# 24S_Sensor_Schematic_v9.net
KiCad netlist of a schematic drawn in EAGLE
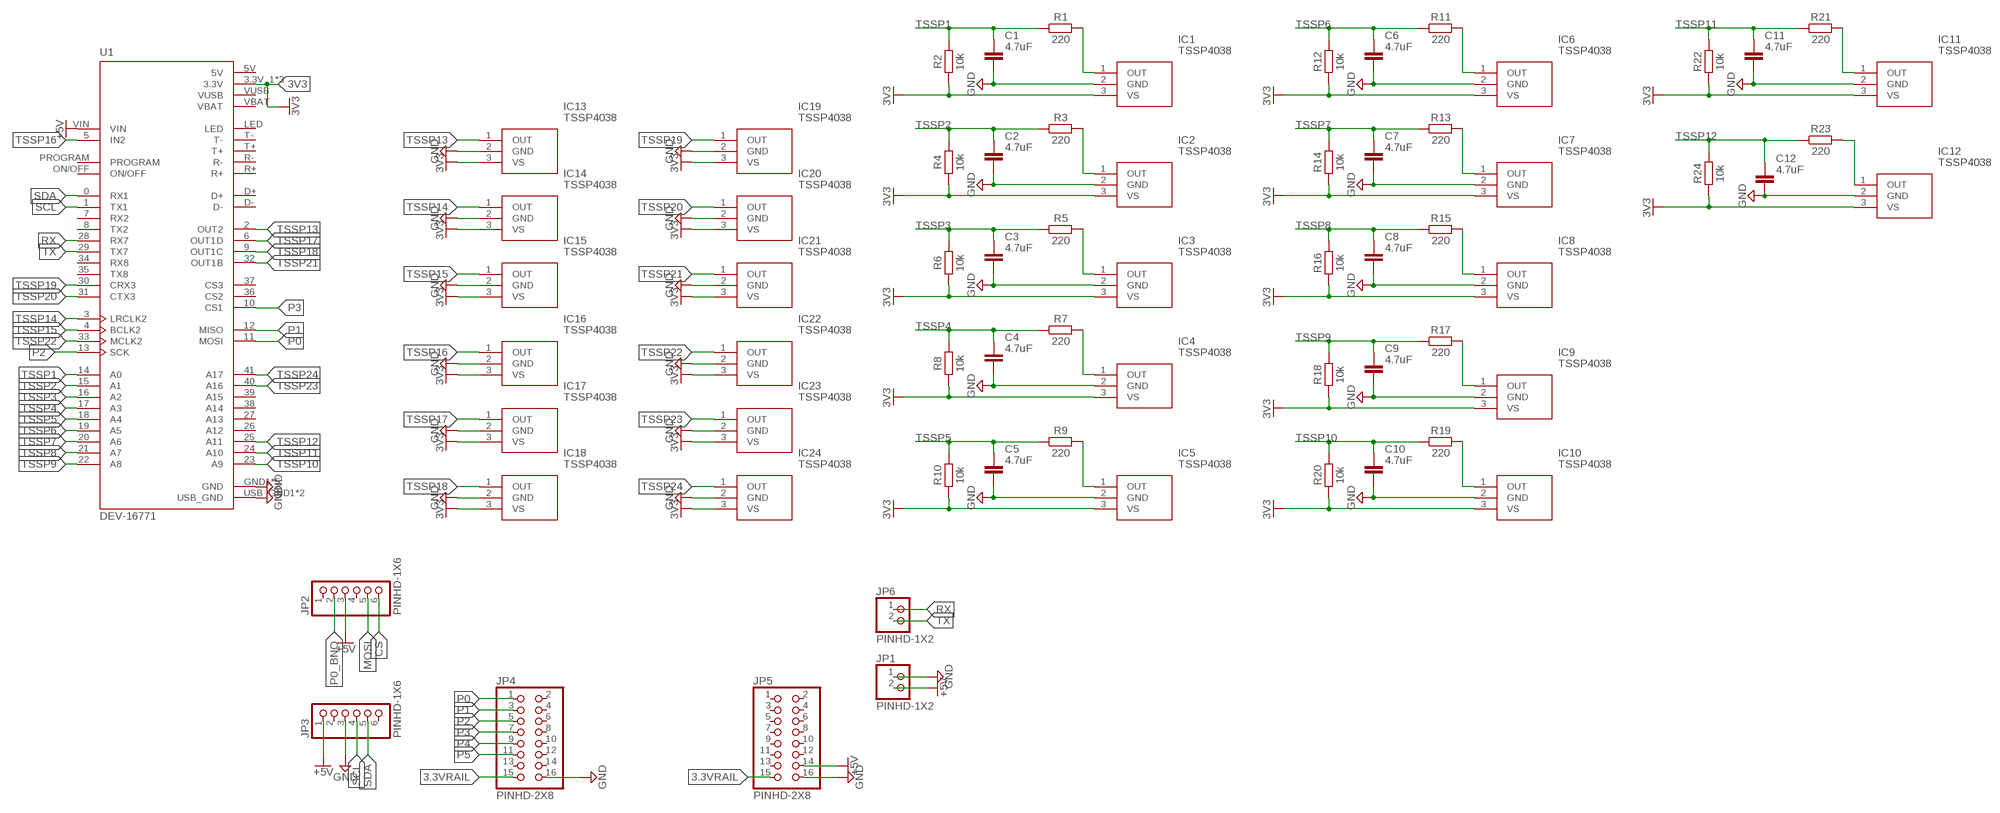
[diagram p0: schematic, sheet 1]

(export (version "E")
  (design (tool "Eeschema 10.0.6"))
  (components
    (comp (ref "C1")
      (value "4.7uF")
      (footprint "eagle-import:CAPC3216X135")
      (libsource (lib "eagle-import") (part "CCHIP-1206(3216-METRIC)_"))
    )
    (comp (ref "C2")
      (value "4.7uF")
      (footprint "eagle-import:CAPC3216X135")
      (libsource (lib "eagle-import") (part "CCHIP-1206(3216-METRIC)_"))
    )
    (comp (ref "C3")
      (value "4.7uF")
      (footprint "eagle-import:CAPC3216X135")
      (libsource (lib "eagle-import") (part "CCHIP-1206(3216-METRIC)_"))
    )
    (comp (ref "C4")
      (value "4.7uF")
      (footprint "eagle-import:CAPC3216X135")
      (libsource (lib "eagle-import") (part "CCHIP-1206(3216-METRIC)_"))
    )
    (comp (ref "C5")
      (value "4.7uF")
      (footprint "eagle-import:CAPC3216X135")
      (libsource (lib "eagle-import") (part "CCHIP-1206(3216-METRIC)_"))
    )
    (comp (ref "C6")
      (value "4.7uF")
      (footprint "eagle-import:CAPC3216X135")
      (libsource (lib "eagle-import") (part "CCHIP-1206(3216-METRIC)_"))
    )
    (comp (ref "C7")
      (value "4.7uF")
      (footprint "eagle-import:CAPC3216X135")
      (libsource (lib "eagle-import") (part "CCHIP-1206(3216-METRIC)_"))
    )
    (comp (ref "C8")
      (value "4.7uF")
      (footprint "eagle-import:CAPC3216X135")
      (libsource (lib "eagle-import") (part "CCHIP-1206(3216-METRIC)_"))
    )
    (comp (ref "C9")
      (value "4.7uF")
      (footprint "eagle-import:CAPC3216X135")
      (libsource (lib "eagle-import") (part "CCHIP-1206(3216-METRIC)_"))
    )
    (comp (ref "C10")
      (value "4.7uF")
      (footprint "eagle-import:CAPC3216X135")
      (libsource (lib "eagle-import") (part "CCHIP-1206(3216-METRIC)_"))
    )
    (comp (ref "C11")
      (value "4.7uF")
      (footprint "eagle-import:CAPC3216X135")
      (libsource (lib "eagle-import") (part "CCHIP-1206(3216-METRIC)_"))
    )
    (comp (ref "C12")
      (value "4.7uF")
      (footprint "eagle-import:CAPC3216X135")
      (libsource (lib "eagle-import") (part "CCHIP-1206(3216-METRIC)_"))
    )
    (comp (ref "IC1")
      (value "TSSP4038")
      (footprint "eagle-import:TSSP4038")
      (fields (field (name "MOUSER_PART_NUMBER") "782-TSSP4038"))
      (libsource (lib "eagle-import") (part "TSSP4038"))
    )
    (comp (ref "IC2")
      (value "TSSP4038")
      (footprint "eagle-import:TSSP4038")
      (fields (field (name "MOUSER_PART_NUMBER") "782-TSSP4038"))
      (libsource (lib "eagle-import") (part "TSSP4038"))
    )
    (comp (ref "IC3")
      (value "TSSP4038")
      (footprint "eagle-import:TSSP4038")
      (fields (field (name "MOUSER_PART_NUMBER") "782-TSSP4038"))
      (libsource (lib "eagle-import") (part "TSSP4038"))
    )
    (comp (ref "IC4")
      (value "TSSP4038")
      (footprint "eagle-import:TSSP4038")
      (fields (field (name "MOUSER_PART_NUMBER") "782-TSSP4038"))
      (libsource (lib "eagle-import") (part "TSSP4038"))
    )
    (comp (ref "IC5")
      (value "TSSP4038")
      (footprint "eagle-import:TSSP4038")
      (fields (field (name "MOUSER_PART_NUMBER") "782-TSSP4038"))
      (libsource (lib "eagle-import") (part "TSSP4038"))
    )
    (comp (ref "IC6")
      (value "TSSP4038")
      (footprint "eagle-import:TSSP4038")
      (fields (field (name "MOUSER_PART_NUMBER") "782-TSSP4038"))
      (libsource (lib "eagle-import") (part "TSSP4038"))
    )
    (comp (ref "IC7")
      (value "TSSP4038")
      (footprint "eagle-import:TSSP4038")
      (fields (field (name "MOUSER_PART_NUMBER") "782-TSSP4038"))
      (libsource (lib "eagle-import") (part "TSSP4038"))
    )
    (comp (ref "IC8")
      (value "TSSP4038")
      (footprint "eagle-import:TSSP4038")
      (fields (field (name "MOUSER_PART_NUMBER") "782-TSSP4038"))
      (libsource (lib "eagle-import") (part "TSSP4038"))
    )
    (comp (ref "IC9")
      (value "TSSP4038")
      (footprint "eagle-import:TSSP4038")
      (fields (field (name "MOUSER_PART_NUMBER") "782-TSSP4038"))
      (libsource (lib "eagle-import") (part "TSSP4038"))
    )
    (comp (ref "IC10")
      (value "TSSP4038")
      (footprint "eagle-import:TSSP4038")
      (fields (field (name "MOUSER_PART_NUMBER") "782-TSSP4038"))
      (libsource (lib "eagle-import") (part "TSSP4038"))
    )
    (comp (ref "IC11")
      (value "TSSP4038")
      (footprint "eagle-import:TSSP4038")
      (fields (field (name "MOUSER_PART_NUMBER") "782-TSSP4038"))
      (libsource (lib "eagle-import") (part "TSSP4038"))
    )
    (comp (ref "IC12")
      (value "TSSP4038")
      (footprint "eagle-import:TSSP4038")
      (fields (field (name "MOUSER_PART_NUMBER") "782-TSSP4038"))
      (libsource (lib "eagle-import") (part "TSSP4038"))
    )
    (comp (ref "IC13")
      (value "TSSP4038")
      (footprint "eagle-import:TSSP4038")
      (fields (field (name "MOUSER_PART_NUMBER") "782-TSSP4038"))
      (libsource (lib "eagle-import") (part "TSSP4038"))
    )
    (comp (ref "IC14")
      (value "TSSP4038")
      (footprint "eagle-import:TSSP4038")
      (fields (field (name "MOUSER_PART_NUMBER") "782-TSSP4038"))
      (libsource (lib "eagle-import") (part "TSSP4038"))
    )
    (comp (ref "IC15")
      (value "TSSP4038")
      (footprint "eagle-import:TSSP4038")
      (fields (field (name "MOUSER_PART_NUMBER") "782-TSSP4038"))
      (libsource (lib "eagle-import") (part "TSSP4038"))
    )
    (comp (ref "IC16")
      (value "TSSP4038")
      (footprint "eagle-import:TSSP4038")
      (fields (field (name "MOUSER_PART_NUMBER") "782-TSSP4038"))
      (libsource (lib "eagle-import") (part "TSSP4038"))
    )
    (comp (ref "IC17")
      (value "TSSP4038")
      (footprint "eagle-import:TSSP4038")
      (fields (field (name "MOUSER_PART_NUMBER") "782-TSSP4038"))
      (libsource (lib "eagle-import") (part "TSSP4038"))
    )
    (comp (ref "IC18")
      (value "TSSP4038")
      (footprint "eagle-import:TSSP4038")
      (fields (field (name "MOUSER_PART_NUMBER") "782-TSSP4038"))
      (libsource (lib "eagle-import") (part "TSSP4038"))
    )
    (comp (ref "IC19")
      (value "TSSP4038")
      (footprint "eagle-import:TSSP4038")
      (fields (field (name "MOUSER_PART_NUMBER") "782-TSSP4038"))
      (libsource (lib "eagle-import") (part "TSSP4038"))
    )
    (comp (ref "IC20")
      (value "TSSP4038")
      (footprint "eagle-import:TSSP4038")
      (fields (field (name "MOUSER_PART_NUMBER") "782-TSSP4038"))
      (libsource (lib "eagle-import") (part "TSSP4038"))
    )
    (comp (ref "IC21")
      (value "TSSP4038")
      (footprint "eagle-import:TSSP4038")
      (fields (field (name "MOUSER_PART_NUMBER") "782-TSSP4038"))
      (libsource (lib "eagle-import") (part "TSSP4038"))
    )
    (comp (ref "IC22")
      (value "TSSP4038")
      (footprint "eagle-import:TSSP4038")
      (fields (field (name "MOUSER_PART_NUMBER") "782-TSSP4038"))
      (libsource (lib "eagle-import") (part "TSSP4038"))
    )
    (comp (ref "IC23")
      (value "TSSP4038")
      (footprint "eagle-import:TSSP4038")
      (fields (field (name "MOUSER_PART_NUMBER") "782-TSSP4038"))
      (libsource (lib "eagle-import") (part "TSSP4038"))
    )
    (comp (ref "IC24")
      (value "TSSP4038")
      (footprint "eagle-import:TSSP4038")
      (fields (field (name "MOUSER_PART_NUMBER") "782-TSSP4038"))
      (libsource (lib "eagle-import") (part "TSSP4038"))
    )
    (comp (ref "JP1")
      (value "PINHD-1X2")
      (footprint "eagle-import:1X02")
      (fields (field (name "MANUFACTURER") "Generic"))
      (libsource (lib "eagle-import") (part "PINHD-1X2"))
    )
    (comp (ref "JP2")
      (value "PINHD-1X6")
      (footprint "eagle-import:1X06")
      (fields (field (name "MANUFACTURER") "Generic"))
      (libsource (lib "eagle-import") (part "PINHD-1X6"))
    )
    (comp (ref "JP3")
      (value "PINHD-1X6")
      (footprint "eagle-import:1X06")
      (fields (field (name "MANUFACTURER") "Generic"))
      (libsource (lib "eagle-import") (part "PINHD-1X6"))
    )
    (comp (ref "JP4")
      (value "PINHD-2X8")
      (footprint "eagle-import:2X08")
      (fields (field (name "MANUFACTURER") "Generic"))
      (libsource (lib "eagle-import") (part "PINHD-2X8"))
    )
    (comp (ref "JP5")
      (value "PINHD-2X8")
      (footprint "eagle-import:2X08")
      (fields (field (name "MANUFACTURER") "Generic"))
      (libsource (lib "eagle-import") (part "PINHD-2X8"))
    )
    (comp (ref "JP6")
      (value "PINHD-1X2")
      (footprint "eagle-import:1X02")
      (fields (field (name "MANUFACTURER") "Generic"))
      (libsource (lib "eagle-import") (part "PINHD-1X2"))
    )
    (comp (ref "R1")
      (value "220")
      (footprint "eagle-import:RESC3216X70")
      (libsource (lib "eagle-import") (part "RCHIP-1206(3216-METRIC)_"))
    )
    (comp (ref "R2")
      (value "10k")
      (footprint "eagle-import:RESC3216X70")
      (libsource (lib "eagle-import") (part "RCHIP-1206(3216-METRIC)_"))
    )
    (comp (ref "R3")
      (value "220")
      (footprint "eagle-import:RESC3216X70")
      (libsource (lib "eagle-import") (part "RCHIP-1206(3216-METRIC)_"))
    )
    (comp (ref "R4")
      (value "10k")
      (footprint "eagle-import:RESC3216X70")
      (libsource (lib "eagle-import") (part "RCHIP-1206(3216-METRIC)_"))
    )
    (comp (ref "R5")
      (value "220")
      (footprint "eagle-import:RESC3216X70")
      (libsource (lib "eagle-import") (part "RCHIP-1206(3216-METRIC)_"))
    )
    (comp (ref "R6")
      (value "10k")
      (footprint "eagle-import:RESC3216X70")
      (libsource (lib "eagle-import") (part "RCHIP-1206(3216-METRIC)_"))
    )
    (comp (ref "R7")
      (value "220")
      (footprint "eagle-import:RESC3216X70")
      (libsource (lib "eagle-import") (part "RCHIP-1206(3216-METRIC)_"))
    )
    (comp (ref "R8")
      (value "10k")
      (footprint "eagle-import:RESC3216X70")
      (libsource (lib "eagle-import") (part "RCHIP-1206(3216-METRIC)_"))
    )
    (comp (ref "R9")
      (value "220")
      (footprint "eagle-import:RESC3216X70")
      (libsource (lib "eagle-import") (part "RCHIP-1206(3216-METRIC)_"))
    )
    (comp (ref "R10")
      (value "10k")
      (footprint "eagle-import:RESC3216X70")
      (libsource (lib "eagle-import") (part "RCHIP-1206(3216-METRIC)_"))
    )
    (comp (ref "R11")
      (value "220")
      (footprint "eagle-import:RESC3216X70")
      (libsource (lib "eagle-import") (part "RCHIP-1206(3216-METRIC)_"))
    )
    (comp (ref "R12")
      (value "10k")
      (footprint "eagle-import:RESC3216X70")
      (libsource (lib "eagle-import") (part "RCHIP-1206(3216-METRIC)_"))
    )
    (comp (ref "R13")
      (value "220")
      (footprint "eagle-import:RESC3216X70")
      (libsource (lib "eagle-import") (part "RCHIP-1206(3216-METRIC)_"))
    )
    (comp (ref "R14")
      (value "10k")
      (footprint "eagle-import:RESC3216X70")
      (libsource (lib "eagle-import") (part "RCHIP-1206(3216-METRIC)_"))
    )
    (comp (ref "R15")
      (value "220")
      (footprint "eagle-import:RESC3216X70")
      (libsource (lib "eagle-import") (part "RCHIP-1206(3216-METRIC)_"))
    )
    (comp (ref "R16")
      (value "10k")
      (footprint "eagle-import:RESC3216X70")
      (libsource (lib "eagle-import") (part "RCHIP-1206(3216-METRIC)_"))
    )
    (comp (ref "R17")
      (value "220")
      (footprint "eagle-import:RESC3216X70")
      (libsource (lib "eagle-import") (part "RCHIP-1206(3216-METRIC)_"))
    )
    (comp (ref "R18")
      (value "10k")
      (footprint "eagle-import:RESC3216X70")
      (libsource (lib "eagle-import") (part "RCHIP-1206(3216-METRIC)_"))
    )
    (comp (ref "R19")
      (value "220")
      (footprint "eagle-import:RESC3216X70")
      (libsource (lib "eagle-import") (part "RCHIP-1206(3216-METRIC)_"))
    )
    (comp (ref "R20")
      (value "10k")
      (footprint "eagle-import:RESC3216X70")
      (libsource (lib "eagle-import") (part "RCHIP-1206(3216-METRIC)_"))
    )
    (comp (ref "R21")
      (value "220")
      (footprint "eagle-import:RESC3216X70")
      (libsource (lib "eagle-import") (part "RCHIP-1206(3216-METRIC)_"))
    )
    (comp (ref "R22")
      (value "10k")
      (footprint "eagle-import:RESC3216X70")
      (libsource (lib "eagle-import") (part "RCHIP-1206(3216-METRIC)_"))
    )
    (comp (ref "R23")
      (value "220")
      (footprint "eagle-import:RESC3216X70")
      (libsource (lib "eagle-import") (part "RCHIP-1206(3216-METRIC)_"))
    )
    (comp (ref "R24")
      (value "10k")
      (footprint "eagle-import:RESC3216X70")
      (libsource (lib "eagle-import") (part "RCHIP-1206(3216-METRIC)_"))
    )
    (comp (ref "U1")
      (value "DEV-16771")
      (footprint "eagle-import:MODULE_DEV-16771")
      (fields (field (name "MF") "SparkFun Electronics"))
      (libsource (lib "eagle-import") (part "DEV-16771"))
    )
  )
  (nets
    (net (code "1") (name "+5V") (class "Default")
      (node (ref "JP1") (pin "2") (pinfunction "2_2") (pintype "passive"))
      (node (ref "JP2") (pin "3") (pinfunction "3_3") (pintype "passive"))
      (node (ref "JP3") (pin "1") (pinfunction "1_1") (pintype "passive"))
      (node (ref "JP5") (pin "14") (pinfunction "14_14") (pintype "passive"))
      (node (ref "U1") (pin "VIN") (pinfunction "VIN_VIN") (pintype "input"))
    )
    (net (code "2") (name "/5V") (class "Default")
      (node (ref "U1") (pin "5V") (pinfunction "5V_5V") (pintype "power_in"))
    )
    (net (code "3") (name "3.3VRAIL") (class "Default")
      (node (ref "JP4") (pin "15") (pinfunction "15_15") (pintype "passive"))
      (node (ref "JP5") (pin "15") (pinfunction "15_15") (pintype "passive"))
    )
    (net (code "4") (name "3V3") (class "Default")
      (node (ref "IC1") (pin "3") (pinfunction "VS_3") (pintype "bidirectional"))
      (node (ref "IC10") (pin "3") (pinfunction "VS_3") (pintype "bidirectional"))
      (node (ref "IC11") (pin "3") (pinfunction "VS_3") (pintype "bidirectional"))
      (node (ref "IC12") (pin "3") (pinfunction "VS_3") (pintype "bidirectional"))
      (node (ref "IC13") (pin "3") (pinfunction "VS_3") (pintype "bidirectional"))
      (node (ref "IC14") (pin "3") (pinfunction "VS_3") (pintype "bidirectional"))
      (node (ref "IC15") (pin "3") (pinfunction "VS_3") (pintype "bidirectional"))
      (node (ref "IC16") (pin "3") (pinfunction "VS_3") (pintype "bidirectional"))
      (node (ref "IC17") (pin "3") (pinfunction "VS_3") (pintype "bidirectional"))
      (node (ref "IC18") (pin "3") (pinfunction "VS_3") (pintype "bidirectional"))
      (node (ref "IC19") (pin "3") (pinfunction "VS_3") (pintype "bidirectional"))
      (node (ref "IC2") (pin "3") (pinfunction "VS_3") (pintype "bidirectional"))
      (node (ref "IC20") (pin "3") (pinfunction "VS_3") (pintype "bidirectional"))
      (node (ref "IC21") (pin "3") (pinfunction "VS_3") (pintype "bidirectional"))
      (node (ref "IC22") (pin "3") (pinfunction "VS_3") (pintype "bidirectional"))
      (node (ref "IC23") (pin "3") (pinfunction "VS_3") (pintype "bidirectional"))
      (node (ref "IC24") (pin "3") (pinfunction "VS_3") (pintype "bidirectional"))
      (node (ref "IC3") (pin "3") (pinfunction "VS_3") (pintype "bidirectional"))
      (node (ref "IC4") (pin "3") (pinfunction "VS_3") (pintype "bidirectional"))
      (node (ref "IC5") (pin "3") (pinfunction "VS_3") (pintype "bidirectional"))
      (node (ref "IC6") (pin "3") (pinfunction "VS_3") (pintype "bidirectional"))
      (node (ref "IC7") (pin "3") (pinfunction "VS_3") (pintype "bidirectional"))
      (node (ref "IC8") (pin "3") (pinfunction "VS_3") (pintype "bidirectional"))
      (node (ref "IC9") (pin "3") (pinfunction "VS_3") (pintype "bidirectional"))
      (node (ref "R10") (pin "1") (pinfunction "1_1") (pintype "passive"))
      (node (ref "R12") (pin "1") (pinfunction "1_1") (pintype "passive"))
      (node (ref "R14") (pin "1") (pinfunction "1_1") (pintype "passive"))
      (node (ref "R16") (pin "1") (pinfunction "1_1") (pintype "passive"))
      (node (ref "R18") (pin "1") (pinfunction "1_1") (pintype "passive"))
      (node (ref "R2") (pin "1") (pinfunction "1_1") (pintype "passive"))
      (node (ref "R20") (pin "1") (pinfunction "1_1") (pintype "passive"))
      (node (ref "R22") (pin "1") (pinfunction "1_1") (pintype "passive"))
      (node (ref "R24") (pin "1") (pinfunction "1_1") (pintype "passive"))
      (node (ref "R4") (pin "1") (pinfunction "1_1") (pintype "passive"))
      (node (ref "R6") (pin "1") (pinfunction "1_1") (pintype "passive"))
      (node (ref "R8") (pin "1") (pinfunction "1_1") (pintype "passive"))
      (node (ref "U1") (pin "3.3V_1") (pinfunction "3.3V_3.3V_1") (pintype "power_in"))
      (node (ref "U1") (pin "3.3V_2") (pinfunction "3.3V_3.3V_2") (pintype "power_in"))
      (node (ref "U1") (pin "3.3V_3") (pinfunction "3.3V_3.3V_3") (pintype "power_in"))
    )
    (net (code "5") (name "CS") (class "Default")
      (node (ref "JP2") (pin "6") (pinfunction "6_6") (pintype "passive"))
    )
    (net (code "6") (name "GND") (class "Default")
      (node (ref "C1") (pin "2") (pinfunction "2_2") (pintype "passive"))
      (node (ref "C10") (pin "2") (pinfunction "2_2") (pintype "passive"))
      (node (ref "C11") (pin "2") (pinfunction "2_2") (pintype "passive"))
      (node (ref "C12") (pin "2") (pinfunction "2_2") (pintype "passive"))
      (node (ref "C2") (pin "2") (pinfunction "2_2") (pintype "passive"))
      (node (ref "C3") (pin "2") (pinfunction "2_2") (pintype "passive"))
      (node (ref "C4") (pin "2") (pinfunction "2_2") (pintype "passive"))
      (node (ref "C5") (pin "2") (pinfunction "2_2") (pintype "passive"))
      (node (ref "C6") (pin "2") (pinfunction "2_2") (pintype "passive"))
      (node (ref "C7") (pin "2") (pinfunction "2_2") (pintype "passive"))
      (node (ref "C8") (pin "2") (pinfunction "2_2") (pintype "passive"))
      (node (ref "C9") (pin "2") (pinfunction "2_2") (pintype "passive"))
      (node (ref "IC1") (pin "2") (pinfunction "GND_2") (pintype "bidirectional"))
      (node (ref "IC10") (pin "2") (pinfunction "GND_2") (pintype "bidirectional"))
      (node (ref "IC11") (pin "2") (pinfunction "GND_2") (pintype "bidirectional"))
      (node (ref "IC12") (pin "2") (pinfunction "GND_2") (pintype "bidirectional"))
      (node (ref "IC13") (pin "2") (pinfunction "GND_2") (pintype "bidirectional"))
      (node (ref "IC14") (pin "2") (pinfunction "GND_2") (pintype "bidirectional"))
      (node (ref "IC15") (pin "2") (pinfunction "GND_2") (pintype "bidirectional"))
      (node (ref "IC16") (pin "2") (pinfunction "GND_2") (pintype "bidirectional"))
      (node (ref "IC17") (pin "2") (pinfunction "GND_2") (pintype "bidirectional"))
      (node (ref "IC18") (pin "2") (pinfunction "GND_2") (pintype "bidirectional"))
      (node (ref "IC19") (pin "2") (pinfunction "GND_2") (pintype "bidirectional"))
      (node (ref "IC2") (pin "2") (pinfunction "GND_2") (pintype "bidirectional"))
      (node (ref "IC20") (pin "2") (pinfunction "GND_2") (pintype "bidirectional"))
      (node (ref "IC21") (pin "2") (pinfunction "GND_2") (pintype "bidirectional"))
      (node (ref "IC22") (pin "2") (pinfunction "GND_2") (pintype "bidirectional"))
      (node (ref "IC23") (pin "2") (pinfunction "GND_2") (pintype "bidirectional"))
      (node (ref "IC24") (pin "2") (pinfunction "GND_2") (pintype "bidirectional"))
      (node (ref "IC3") (pin "2") (pinfunction "GND_2") (pintype "bidirectional"))
      (node (ref "IC4") (pin "2") (pinfunction "GND_2") (pintype "bidirectional"))
      (node (ref "IC5") (pin "2") (pinfunction "GND_2") (pintype "bidirectional"))
      (node (ref "IC6") (pin "2") (pinfunction "GND_2") (pintype "bidirectional"))
      (node (ref "IC7") (pin "2") (pinfunction "GND_2") (pintype "bidirectional"))
      (node (ref "IC8") (pin "2") (pinfunction "GND_2") (pintype "bidirectional"))
      (node (ref "IC9") (pin "2") (pinfunction "GND_2") (pintype "bidirectional"))
      (node (ref "JP1") (pin "1") (pinfunction "1_1") (pintype "passive"))
      (node (ref "JP3") (pin "3") (pinfunction "3_3") (pintype "passive"))
      (node (ref "JP4") (pin "16") (pinfunction "16_16") (pintype "passive"))
      (node (ref "JP5") (pin "16") (pinfunction "16_16") (pintype "passive"))
      (node (ref "U1") (pin "GND1") (pinfunction "GND_GND1") (pintype "power_in"))
      (node (ref "U1") (pin "GND2") (pinfunction "GND_GND2") (pintype "power_in"))
      (node (ref "U1") (pin "GND3") (pinfunction "GND_GND3") (pintype "power_in"))
      (node (ref "U1") (pin "GND4") (pinfunction "GND_GND4") (pintype "power_in"))
      (node (ref "U1") (pin "GND5") (pinfunction "GND_GND5") (pintype "power_in"))
      (node (ref "U1") (pin "USB_GND1") (pinfunction "USB_GND_USB_GND1") (pintype "power_in"))
      (node (ref "U1") (pin "USB_GND2") (pinfunction "USB_GND_USB_GND2") (pintype "power_in"))
    )
    (net (code "7") (name "MOSI") (class "Default")
      (node (ref "JP2") (pin "5") (pinfunction "5_5") (pintype "passive"))
    )
    (net (code "8") (name "Net-(IC1-OUT)") (class "Default")
      (node (ref "IC1") (pin "1") (pinfunction "OUT_1") (pintype "bidirectional"))
      (node (ref "R1") (pin "2") (pinfunction "2_2") (pintype "passive"))
    )
    (net (code "9") (name "Net-(IC2-OUT)") (class "Default")
      (node (ref "IC2") (pin "1") (pinfunction "OUT_1") (pintype "bidirectional"))
      (node (ref "R3") (pin "2") (pinfunction "2_2") (pintype "passive"))
    )
    (net (code "10") (name "Net-(IC3-OUT)") (class "Default")
      (node (ref "IC3") (pin "1") (pinfunction "OUT_1") (pintype "bidirectional"))
      (node (ref "R5") (pin "2") (pinfunction "2_2") (pintype "passive"))
    )
    (net (code "11") (name "Net-(IC4-OUT)") (class "Default")
      (node (ref "IC4") (pin "1") (pinfunction "OUT_1") (pintype "bidirectional"))
      (node (ref "R7") (pin "2") (pinfunction "2_2") (pintype "passive"))
    )
    (net (code "12") (name "Net-(IC5-OUT)") (class "Default")
      (node (ref "IC5") (pin "1") (pinfunction "OUT_1") (pintype "bidirectional"))
      (node (ref "R9") (pin "2") (pinfunction "2_2") (pintype "passive"))
    )
    (net (code "13") (name "Net-(IC6-OUT)") (class "Default")
      (node (ref "IC6") (pin "1") (pinfunction "OUT_1") (pintype "bidirectional"))
      (node (ref "R11") (pin "2") (pinfunction "2_2") (pintype "passive"))
    )
    (net (code "14") (name "Net-(IC7-OUT)") (class "Default")
      (node (ref "IC7") (pin "1") (pinfunction "OUT_1") (pintype "bidirectional"))
      (node (ref "R13") (pin "2") (pinfunction "2_2") (pintype "passive"))
    )
    (net (code "15") (name "Net-(IC8-OUT)") (class "Default")
      (node (ref "IC8") (pin "1") (pinfunction "OUT_1") (pintype "bidirectional"))
      (node (ref "R15") (pin "2") (pinfunction "2_2") (pintype "passive"))
    )
    (net (code "16") (name "Net-(IC9-OUT)") (class "Default")
      (node (ref "IC9") (pin "1") (pinfunction "OUT_1") (pintype "bidirectional"))
      (node (ref "R17") (pin "2") (pinfunction "2_2") (pintype "passive"))
    )
    (net (code "17") (name "Net-(IC10-OUT)") (class "Default")
      (node (ref "IC10") (pin "1") (pinfunction "OUT_1") (pintype "bidirectional"))
      (node (ref "R19") (pin "2") (pinfunction "2_2") (pintype "passive"))
    )
    (net (code "18") (name "Net-(IC11-OUT)") (class "Default")
      (node (ref "IC11") (pin "1") (pinfunction "OUT_1") (pintype "bidirectional"))
      (node (ref "R21") (pin "2") (pinfunction "2_2") (pintype "passive"))
    )
    (net (code "19") (name "Net-(IC12-OUT)") (class "Default")
      (node (ref "IC12") (pin "1") (pinfunction "OUT_1") (pintype "bidirectional"))
      (node (ref "R23") (pin "2") (pinfunction "2_2") (pintype "passive"))
    )
    (net (code "20") (name "P0") (class "Default")
      (node (ref "JP4") (pin "1") (pinfunction "1_1") (pintype "passive"))
      (node (ref "U1") (pin "11") (pinfunction "MOSI_11") (pintype "bidirectional"))
    )
    (net (code "21") (name "P0_BNO") (class "Default")
      (node (ref "JP2") (pin "2") (pinfunction "2_2") (pintype "passive"))
    )
    (net (code "22") (name "P1") (class "Default")
      (node (ref "JP4") (pin "3") (pinfunction "3_3") (pintype "passive"))
      (node (ref "U1") (pin "12") (pinfunction "MISO_12") (pintype "bidirectional"))
    )
    (net (code "23") (name "P2") (class "Default")
      (node (ref "JP4") (pin "5") (pinfunction "5_5") (pintype "passive"))
      (node (ref "U1") (pin "13") (pinfunction "SCK_13") (pintype "bidirectional"))
    )
    (net (code "24") (name "P3") (class "Default")
      (node (ref "JP4") (pin "7") (pinfunction "7_7") (pintype "passive"))
      (node (ref "U1") (pin "10") (pinfunction "CS1_10") (pintype "bidirectional"))
    )
    (net (code "25") (name "P4") (class "Default")
      (node (ref "JP4") (pin "9") (pinfunction "9_9") (pintype "passive"))
    )
    (net (code "26") (name "P5") (class "Default")
      (node (ref "JP4") (pin "11") (pinfunction "11_11") (pintype "passive"))
    )
    (net (code "27") (name "RX") (class "Default")
      (node (ref "JP6") (pin "1") (pinfunction "1_1") (pintype "passive"))
      (node (ref "U1") (pin "28") (pinfunction "RX7_28") (pintype "bidirectional"))
    )
    (net (code "28") (name "SCL") (class "Default")
      (node (ref "JP3") (pin "4") (pinfunction "4_4") (pintype "passive"))
      (node (ref "U1") (pin "1") (pinfunction "TX1_1") (pintype "bidirectional"))
    )
    (net (code "29") (name "SDA") (class "Default")
      (node (ref "JP3") (pin "5") (pinfunction "5_5") (pintype "passive"))
      (node (ref "U1") (pin "0") (pinfunction "RX1_0") (pintype "bidirectional"))
    )
    (net (code "30") (name "TSSP1") (class "Default")
      (node (ref "C1") (pin "1") (pinfunction "1_1") (pintype "passive"))
      (node (ref "R1") (pin "1") (pinfunction "1_1") (pintype "passive"))
      (node (ref "R2") (pin "2") (pinfunction "2_2") (pintype "passive"))
      (node (ref "U1") (pin "14") (pinfunction "A0_14") (pintype "bidirectional"))
    )
    (net (code "31") (name "TSSP2") (class "Default")
      (node (ref "C2") (pin "1") (pinfunction "1_1") (pintype "passive"))
      (node (ref "R3") (pin "1") (pinfunction "1_1") (pintype "passive"))
      (node (ref "R4") (pin "2") (pinfunction "2_2") (pintype "passive"))
      (node (ref "U1") (pin "15") (pinfunction "A1_15") (pintype "bidirectional"))
    )
    (net (code "32") (name "TSSP3") (class "Default")
      (node (ref "C3") (pin "1") (pinfunction "1_1") (pintype "passive"))
      (node (ref "R5") (pin "1") (pinfunction "1_1") (pintype "passive"))
      (node (ref "R6") (pin "2") (pinfunction "2_2") (pintype "passive"))
      (node (ref "U1") (pin "16") (pinfunction "A2_16") (pintype "bidirectional"))
    )
    (net (code "33") (name "TSSP4") (class "Default")
      (node (ref "C4") (pin "1") (pinfunction "1_1") (pintype "passive"))
      (node (ref "R7") (pin "1") (pinfunction "1_1") (pintype "passive"))
      (node (ref "R8") (pin "2") (pinfunction "2_2") (pintype "passive"))
      (node (ref "U1") (pin "17") (pinfunction "A3_17") (pintype "bidirectional"))
    )
    (net (code "34") (name "TSSP5") (class "Default")
      (node (ref "C5") (pin "1") (pinfunction "1_1") (pintype "passive"))
      (node (ref "R10") (pin "2") (pinfunction "2_2") (pintype "passive"))
      (node (ref "R9") (pin "1") (pinfunction "1_1") (pintype "passive"))
      (node (ref "U1") (pin "18") (pinfunction "A4_18") (pintype "bidirectional"))
    )
    (net (code "35") (name "TSSP6") (class "Default")
      (node (ref "C6") (pin "1") (pinfunction "1_1") (pintype "passive"))
      (node (ref "R11") (pin "1") (pinfunction "1_1") (pintype "passive"))
      (node (ref "R12") (pin "2") (pinfunction "2_2") (pintype "passive"))
      (node (ref "U1") (pin "19") (pinfunction "A5_19") (pintype "bidirectional"))
    )
    (net (code "36") (name "TSSP7") (class "Default")
      (node (ref "C7") (pin "1") (pinfunction "1_1") (pintype "passive"))
      (node (ref "R13") (pin "1") (pinfunction "1_1") (pintype "passive"))
      (node (ref "R14") (pin "2") (pinfunction "2_2") (pintype "passive"))
      (node (ref "U1") (pin "20") (pinfunction "A6_20") (pintype "bidirectional"))
    )
    (net (code "37") (name "TSSP8") (class "Default")
      (node (ref "C8") (pin "1") (pinfunction "1_1") (pintype "passive"))
      (node (ref "R15") (pin "1") (pinfunction "1_1") (pintype "passive"))
      (node (ref "R16") (pin "2") (pinfunction "2_2") (pintype "passive"))
      (node (ref "U1") (pin "21") (pinfunction "A7_21") (pintype "bidirectional"))
    )
    (net (code "38") (name "TSSP9") (class "Default")
      (node (ref "C9") (pin "1") (pinfunction "1_1") (pintype "passive"))
      (node (ref "R17") (pin "1") (pinfunction "1_1") (pintype "passive"))
      (node (ref "R18") (pin "2") (pinfunction "2_2") (pintype "passive"))
      (node (ref "U1") (pin "22") (pinfunction "A8_22") (pintype "bidirectional"))
    )
    (net (code "39") (name "TSSP10") (class "Default")
      (node (ref "C10") (pin "1") (pinfunction "1_1") (pintype "passive"))
      (node (ref "R19") (pin "1") (pinfunction "1_1") (pintype "passive"))
      (node (ref "R20") (pin "2") (pinfunction "2_2") (pintype "passive"))
      (node (ref "U1") (pin "23") (pinfunction "A9_23") (pintype "bidirectional"))
    )
    (net (code "40") (name "TSSP11") (class "Default")
      (node (ref "C11") (pin "1") (pinfunction "1_1") (pintype "passive"))
      (node (ref "R21") (pin "1") (pinfunction "1_1") (pintype "passive"))
      (node (ref "R22") (pin "2") (pinfunction "2_2") (pintype "passive"))
      (node (ref "U1") (pin "24") (pinfunction "A10_24") (pintype "bidirectional"))
    )
    (net (code "41") (name "TSSP12") (class "Default")
      (node (ref "C12") (pin "1") (pinfunction "1_1") (pintype "passive"))
      (node (ref "R23") (pin "1") (pinfunction "1_1") (pintype "passive"))
      (node (ref "R24") (pin "2") (pinfunction "2_2") (pintype "passive"))
      (node (ref "U1") (pin "25") (pinfunction "A11_25") (pintype "bidirectional"))
    )
    (net (code "42") (name "TSSP13") (class "Default")
      (node (ref "IC13") (pin "1") (pinfunction "OUT_1") (pintype "bidirectional"))
      (node (ref "U1") (pin "2") (pinfunction "OUT2_2") (pintype "output"))
    )
    (net (code "43") (name "TSSP14") (class "Default")
      (node (ref "IC14") (pin "1") (pinfunction "OUT_1") (pintype "bidirectional"))
      (node (ref "U1") (pin "3") (pinfunction "LRCLK2_3") (pintype "bidirectional"))
    )
    (net (code "44") (name "TSSP15") (class "Default")
      (node (ref "IC15") (pin "1") (pinfunction "OUT_1") (pintype "bidirectional"))
      (node (ref "U1") (pin "4") (pinfunction "BCLK2_4") (pintype "bidirectional"))
    )
    (net (code "45") (name "TSSP16") (class "Default")
      (node (ref "IC16") (pin "1") (pinfunction "OUT_1") (pintype "bidirectional"))
      (node (ref "U1") (pin "5") (pinfunction "IN2_5") (pintype "bidirectional"))
    )
    (net (code "46") (name "TSSP17") (class "Default")
      (node (ref "IC17") (pin "1") (pinfunction "OUT_1") (pintype "bidirectional"))
      (node (ref "U1") (pin "6") (pinfunction "OUT1D_6") (pintype "output"))
    )
    (net (code "47") (name "TSSP18") (class "Default")
      (node (ref "IC18") (pin "1") (pinfunction "OUT_1") (pintype "bidirectional"))
      (node (ref "U1") (pin "9") (pinfunction "OUT1C_9") (pintype "output"))
    )
    (net (code "48") (name "TSSP19") (class "Default")
      (node (ref "IC19") (pin "1") (pinfunction "OUT_1") (pintype "bidirectional"))
      (node (ref "U1") (pin "30") (pinfunction "CRX3_30") (pintype "bidirectional"))
    )
    (net (code "49") (name "TSSP20") (class "Default")
      (node (ref "IC20") (pin "1") (pinfunction "OUT_1") (pintype "bidirectional"))
      (node (ref "U1") (pin "31") (pinfunction "CTX3_31") (pintype "bidirectional"))
    )
    (net (code "50") (name "TSSP21") (class "Default")
      (node (ref "IC21") (pin "1") (pinfunction "OUT_1") (pintype "bidirectional"))
      (node (ref "U1") (pin "32") (pinfunction "OUT1B_32") (pintype "output"))
    )
    (net (code "51") (name "TSSP22") (class "Default")
      (node (ref "IC22") (pin "1") (pinfunction "OUT_1") (pintype "bidirectional"))
      (node (ref "U1") (pin "33") (pinfunction "MCLK2_33") (pintype "bidirectional"))
    )
    (net (code "52") (name "TSSP23") (class "Default")
      (node (ref "IC23") (pin "1") (pinfunction "OUT_1") (pintype "bidirectional"))
      (node (ref "U1") (pin "40") (pinfunction "A16_40") (pintype "bidirectional"))
    )
    (net (code "53") (name "TSSP24") (class "Default")
      (node (ref "IC24") (pin "1") (pinfunction "OUT_1") (pintype "bidirectional"))
      (node (ref "U1") (pin "41") (pinfunction "A17_41") (pintype "bidirectional"))
    )
    (net (code "54") (name "TX") (class "Default")
      (node (ref "JP6") (pin "2") (pinfunction "2_2") (pintype "passive"))
      (node (ref "U1") (pin "29") (pinfunction "TX7_29") (pintype "bidirectional"))
    )
    (net (code "55") (name "unconnected-(JP2-Pad1)") (class "Default")
      (node (ref "JP2") (pin "1") (pinfunction "1_1") (pintype "passive"))
    )
    (net (code "56") (name "unconnected-(JP2-Pad4)") (class "Default")
      (node (ref "JP2") (pin "4") (pinfunction "4_4") (pintype "passive"))
    )
    (net (code "57") (name "unconnected-(JP3-Pad2)") (class "Default")
      (node (ref "JP3") (pin "2") (pinfunction "2_2") (pintype "passive"))
    )
    (net (code "58") (name "unconnected-(JP3-Pad6)") (class "Default")
      (node (ref "JP3") (pin "6") (pinfunction "6_6") (pintype "passive"))
    )
    (net (code "59") (name "unconnected-(JP4-Pad2)") (class "Default")
      (node (ref "JP4") (pin "2") (pinfunction "2_2") (pintype "passive"))
    )
    (net (code "60") (name "unconnected-(JP4-Pad4)") (class "Default")
      (node (ref "JP4") (pin "4") (pinfunction "4_4") (pintype "passive"))
    )
    (net (code "61") (name "unconnected-(JP4-Pad6)") (class "Default")
      (node (ref "JP4") (pin "6") (pinfunction "6_6") (pintype "passive"))
    )
    (net (code "62") (name "unconnected-(JP4-Pad8)") (class "Default")
      (node (ref "JP4") (pin "8") (pinfunction "8_8") (pintype "passive"))
    )
    (net (code "63") (name "unconnected-(JP4-Pad10)") (class "Default")
      (node (ref "JP4") (pin "10") (pinfunction "10_10") (pintype "passive"))
    )
    (net (code "64") (name "unconnected-(JP4-Pad12)") (class "Default")
      (node (ref "JP4") (pin "12") (pinfunction "12_12") (pintype "passive"))
    )
    (net (code "65") (name "unconnected-(JP4-Pad13)") (class "Default")
      (node (ref "JP4") (pin "13") (pinfunction "13_13") (pintype "passive"))
    )
    (net (code "66") (name "unconnected-(JP4-Pad14)") (class "Default")
      (node (ref "JP4") (pin "14") (pinfunction "14_14") (pintype "passive"))
    )
    (net (code "67") (name "unconnected-(JP5-Pad1)") (class "Default")
      (node (ref "JP5") (pin "1") (pinfunction "1_1") (pintype "passive"))
    )
    (net (code "68") (name "unconnected-(JP5-Pad2)") (class "Default")
      (node (ref "JP5") (pin "2") (pinfunction "2_2") (pintype "passive"))
    )
    (net (code "69") (name "unconnected-(JP5-Pad3)") (class "Default")
      (node (ref "JP5") (pin "3") (pinfunction "3_3") (pintype "passive"))
    )
    (net (code "70") (name "unconnected-(JP5-Pad4)") (class "Default")
      (node (ref "JP5") (pin "4") (pinfunction "4_4") (pintype "passive"))
    )
    (net (code "71") (name "unconnected-(JP5-Pad5)") (class "Default")
      (node (ref "JP5") (pin "5") (pinfunction "5_5") (pintype "passive"))
    )
    (net (code "72") (name "unconnected-(JP5-Pad6)") (class "Default")
      (node (ref "JP5") (pin "6") (pinfunction "6_6") (pintype "passive"))
    )
    (net (code "73") (name "unconnected-(JP5-Pad7)") (class "Default")
      (node (ref "JP5") (pin "7") (pinfunction "7_7") (pintype "passive"))
    )
    (net (code "74") (name "unconnected-(JP5-Pad8)") (class "Default")
      (node (ref "JP5") (pin "8") (pinfunction "8_8") (pintype "passive"))
    )
    (net (code "75") (name "unconnected-(JP5-Pad9)") (class "Default")
      (node (ref "JP5") (pin "9") (pinfunction "9_9") (pintype "passive"))
    )
    (net (code "76") (name "unconnected-(JP5-Pad10)") (class "Default")
      (node (ref "JP5") (pin "10") (pinfunction "10_10") (pintype "passive"))
    )
    (net (code "77") (name "unconnected-(JP5-Pad11)") (class "Default")
      (node (ref "JP5") (pin "11") (pinfunction "11_11") (pintype "passive"))
    )
    (net (code "78") (name "unconnected-(JP5-Pad12)") (class "Default")
      (node (ref "JP5") (pin "12") (pinfunction "12_12") (pintype "passive"))
    )
    (net (code "79") (name "unconnected-(JP5-Pad13)") (class "Default")
      (node (ref "JP5") (pin "13") (pinfunction "13_13") (pintype "passive"))
    )
    (net (code "80") (name "unconnected-(U1-A12-Pad26)") (class "Default")
      (node (ref "U1") (pin "26") (pinfunction "A12_26") (pintype "bidirectional"))
    )
    (net (code "81") (name "unconnected-(U1-A13-Pad27)") (class "Default")
      (node (ref "U1") (pin "27") (pinfunction "A13_27") (pintype "bidirectional"))
    )
    (net (code "82") (name "unconnected-(U1-A14-Pad38)") (class "Default")
      (node (ref "U1") (pin "38") (pinfunction "A14_38") (pintype "bidirectional"))
    )
    (net (code "83") (name "unconnected-(U1-A15-Pad39)") (class "Default")
      (node (ref "U1") (pin "39") (pinfunction "A15_39") (pintype "bidirectional"))
    )
    (net (code "84") (name "unconnected-(U1-CS2-Pad36)") (class "Default")
      (node (ref "U1") (pin "36") (pinfunction "CS2_36") (pintype "bidirectional"))
    )
    (net (code "85") (name "unconnected-(U1-CS3-Pad37)") (class "Default")
      (node (ref "U1") (pin "37") (pinfunction "CS3_37") (pintype "bidirectional"))
    )
    (net (code "86") (name "unconnected-(U1-PadD+)") (class "Default")
      (node (ref "U1") (pin "D+") (pinfunction "D+_D+") (pintype "bidirectional"))
    )
    (net (code "87") (name "unconnected-(U1-PadD-)") (class "Default")
      (node (ref "U1") (pin "D-") (pinfunction "D-_D-") (pintype "bidirectional"))
    )
    (net (code "88") (name "unconnected-(U1-PadLED)") (class "Default")
      (node (ref "U1") (pin "LED") (pinfunction "LED_LED") (pintype "bidirectional"))
    )
    (net (code "89") (name "unconnected-(U1-PadON{slash}OFF)") (class "Default")
      (node (ref "U1") (pin "ON/OFF") (pinfunction "ON/OFF_ON/OFF") (pintype "bidirectional"))
    )
    (net (code "90") (name "unconnected-(U1-PadPROGRAM)") (class "Default")
      (node (ref "U1") (pin "PROGRAM") (pinfunction "PROGRAM_PROGRAM") (pintype "bidirectional"))
    )
    (net (code "91") (name "unconnected-(U1-PadR+)") (class "Default")
      (node (ref "U1") (pin "R+") (pinfunction "R+_R+") (pintype "bidirectional"))
    )
    (net (code "92") (name "unconnected-(U1-PadR-)") (class "Default")
      (node (ref "U1") (pin "R-") (pinfunction "R-_R-") (pintype "bidirectional"))
    )
    (net (code "93") (name "unconnected-(U1-PadT+)") (class "Default")
      (node (ref "U1") (pin "T+") (pinfunction "T+_T+") (pintype "bidirectional"))
    )
    (net (code "94") (name "unconnected-(U1-PadT-)") (class "Default")
      (node (ref "U1") (pin "T-") (pinfunction "T-_T-") (pintype "bidirectional"))
    )
    (net (code "95") (name "unconnected-(U1-PadVBAT)") (class "Default")
      (node (ref "U1") (pin "VBAT") (pinfunction "VBAT_VBAT") (pintype "passive"))
    )
    (net (code "96") (name "unconnected-(U1-PadVUSB)") (class "Default")
      (node (ref "U1") (pin "VUSB") (pinfunction "VUSB_VUSB") (pintype "passive"))
    )
    (net (code "97") (name "unconnected-(U1-RX2-Pad7)") (class "Default")
      (node (ref "U1") (pin "7") (pinfunction "RX2_7") (pintype "bidirectional"))
    )
    (net (code "98") (name "unconnected-(U1-RX8-Pad34)") (class "Default")
      (node (ref "U1") (pin "34") (pinfunction "RX8_34") (pintype "bidirectional"))
    )
    (net (code "99") (name "unconnected-(U1-TX2-Pad8)") (class "Default")
      (node (ref "U1") (pin "8") (pinfunction "TX2_8") (pintype "bidirectional"))
    )
    (net (code "100") (name "unconnected-(U1-TX8-Pad35)") (class "Default")
      (node (ref "U1") (pin "35") (pinfunction "TX8_35") (pintype "bidirectional"))
    )
  )
)
